# SMA_Dual_Series_Filter.net
KiCad netlist of a schematic drawn in Altium Designer
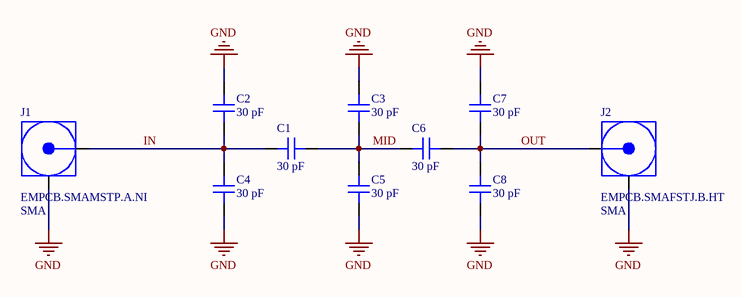
[diagram p0: SMA Dual Series Filter.SchDoc]

(export (version "E")
  (design (tool "Eeschema 10.0.6"))
  (components
    (comp (ref "C1")
      (value "30 pF")
      (footprint "CAP 0402_1005")
      (description "HIGH-Q MLC CAPACITOR, C-SERIES,")
      (fields
        (field (name "PART NUMBER") "QCCF251Q300J1GV001T")
        (field (name "MANUFACTURER") "Johanson Technology Inc.")
      )
      (libsource (lib "altiumlibrary.com") (part "Capacitor"))
    )
    (comp (ref "C2")
      (value "30 pF")
      (footprint "CAP 0402_1005")
      (description "HIGH-Q MLC CAPACITOR, C-SERIES,")
      (fields
        (field (name "PART NUMBER") "QCCF251Q300J1GV001T")
        (field (name "MANUFACTURER") "Johanson Technology Inc.")
      )
      (libsource (lib "altiumlibrary.com") (part "Capacitor"))
    )
    (comp (ref "C3")
      (value "30 pF")
      (footprint "CAP 0402_1005")
      (description "HIGH-Q MLC CAPACITOR, C-SERIES,")
      (fields
        (field (name "PART NUMBER") "QCCF251Q300J1GV001T")
        (field (name "MANUFACTURER") "Johanson Technology Inc.")
      )
      (libsource (lib "altiumlibrary.com") (part "Capacitor"))
    )
    (comp (ref "C4")
      (value "30 pF")
      (footprint "CAP 0402_1005")
      (description "HIGH-Q MLC CAPACITOR, C-SERIES,")
      (fields
        (field (name "PART NUMBER") "QCCF251Q300J1GV001T")
        (field (name "MANUFACTURER") "Johanson Technology Inc.")
      )
      (libsource (lib "altiumlibrary.com") (part "Capacitor"))
    )
    (comp (ref "C5")
      (value "30 pF")
      (footprint "CAP 0402_1005")
      (description "HIGH-Q MLC CAPACITOR, C-SERIES,")
      (fields
        (field (name "PART NUMBER") "QCCF251Q300J1GV001T")
        (field (name "MANUFACTURER") "Johanson Technology Inc.")
      )
      (libsource (lib "altiumlibrary.com") (part "Capacitor"))
    )
    (comp (ref "C6")
      (value "30 pF")
      (footprint "CAP 0402_1005")
      (description "HIGH-Q MLC CAPACITOR, C-SERIES,")
      (fields
        (field (name "PART NUMBER") "QCCF251Q300J1GV001T")
        (field (name "MANUFACTURER") "Johanson Technology Inc.")
      )
      (libsource (lib "altiumlibrary.com") (part "Capacitor"))
    )
    (comp (ref "C7")
      (value "30 pF")
      (footprint "CAP 0402_1005")
      (description "HIGH-Q MLC CAPACITOR, C-SERIES,")
      (fields
        (field (name "PART NUMBER") "QCCF251Q300J1GV001T")
        (field (name "MANUFACTURER") "Johanson Technology Inc.")
      )
      (libsource (lib "altiumlibrary.com") (part "Capacitor"))
    )
    (comp (ref "C8")
      (value "30 pF")
      (footprint "CAP 0402_1005")
      (description "HIGH-Q MLC CAPACITOR, C-SERIES,")
      (fields
        (field (name "PART NUMBER") "QCCF251Q300J1GV001T")
        (field (name "MANUFACTURER") "Johanson Technology Inc.")
      )
      (libsource (lib "altiumlibrary.com") (part "Capacitor"))
    )
    (comp (ref "J1")
      (value "EMPCB.SMAMSTP.A.NI")
      (footprint "TAOGLAS EMPCB.SMAMSTP.A.NI")
      (description "SMA(M)ST FOR PCB EDGE MOUNT NI P")
      (fields (field (name "CONNECTOR STYLE") "SMA") (field (name "MANUFACTURER") "Taoglas Limited"))
      (libsource (lib "altiumlibrary.com") (part "COAX CONNECTOR"))
    )
    (comp (ref "J2")
      (value "EMPCB.SMAFSTJ.B.HT")
      (footprint "TAOGLAS EMPCB.SMAFSTJ.B.HT")
      (description "CONN SMA JACK STR 50OHM EDGE MNT")
      (fields (field (name "CONNECTOR STYLE") "SMA") (field (name "MANUFACTURER") "Taoglas Limited"))
      (libsource (lib "altiumlibrary.com") (part "COAX CONNECTOR"))
    )
  )
  (nets
    (net (code "1") (name "/IN") (class "Default")
      (node (ref "C1") (pin "1") (pinfunction "1_1") (pintype "passive"))
      (node (ref "C2") (pin "1") (pinfunction "1_1") (pintype "passive"))
      (node (ref "C4") (pin "2") (pinfunction "2_2") (pintype "passive"))
      (node (ref "J1") (pin "S") (pinfunction "Signal_S") (pintype "passive"))
    )
    (net (code "2") (name "/MID") (class "Default")
      (node (ref "C1") (pin "2") (pinfunction "2_2") (pintype "passive"))
      (node (ref "C3") (pin "1") (pinfunction "1_1") (pintype "passive"))
      (node (ref "C5") (pin "2") (pinfunction "2_2") (pintype "passive"))
      (node (ref "C6") (pin "2") (pinfunction "2_2") (pintype "passive"))
    )
    (net (code "3") (name "/OUT") (class "Default")
      (node (ref "C6") (pin "1") (pinfunction "1_1") (pintype "passive"))
      (node (ref "C7") (pin "1") (pinfunction "1_1") (pintype "passive"))
      (node (ref "C8") (pin "2") (pinfunction "2_2") (pintype "passive"))
      (node (ref "J2") (pin "S") (pinfunction "Signal_S") (pintype "passive"))
    )
    (net (code "4") (name "GND") (class "Default")
      (node (ref "C2") (pin "2") (pinfunction "2_2") (pintype "passive"))
      (node (ref "C3") (pin "2") (pinfunction "2_2") (pintype "passive"))
      (node (ref "C4") (pin "1") (pinfunction "1_1") (pintype "passive"))
      (node (ref "C5") (pin "1") (pinfunction "1_1") (pintype "passive"))
      (node (ref "C7") (pin "2") (pinfunction "2_2") (pintype "passive"))
      (node (ref "C8") (pin "1") (pinfunction "1_1") (pintype "passive"))
      (node (ref "J1") (pin "G") (pinfunction "GND_G") (pintype "passive"))
      (node (ref "J2") (pin "G") (pinfunction "GND_G") (pintype "passive"))
    )
  )
)
